# Rotary_Switches.net
KiCad netlist of a schematic drawn in Altium Designer
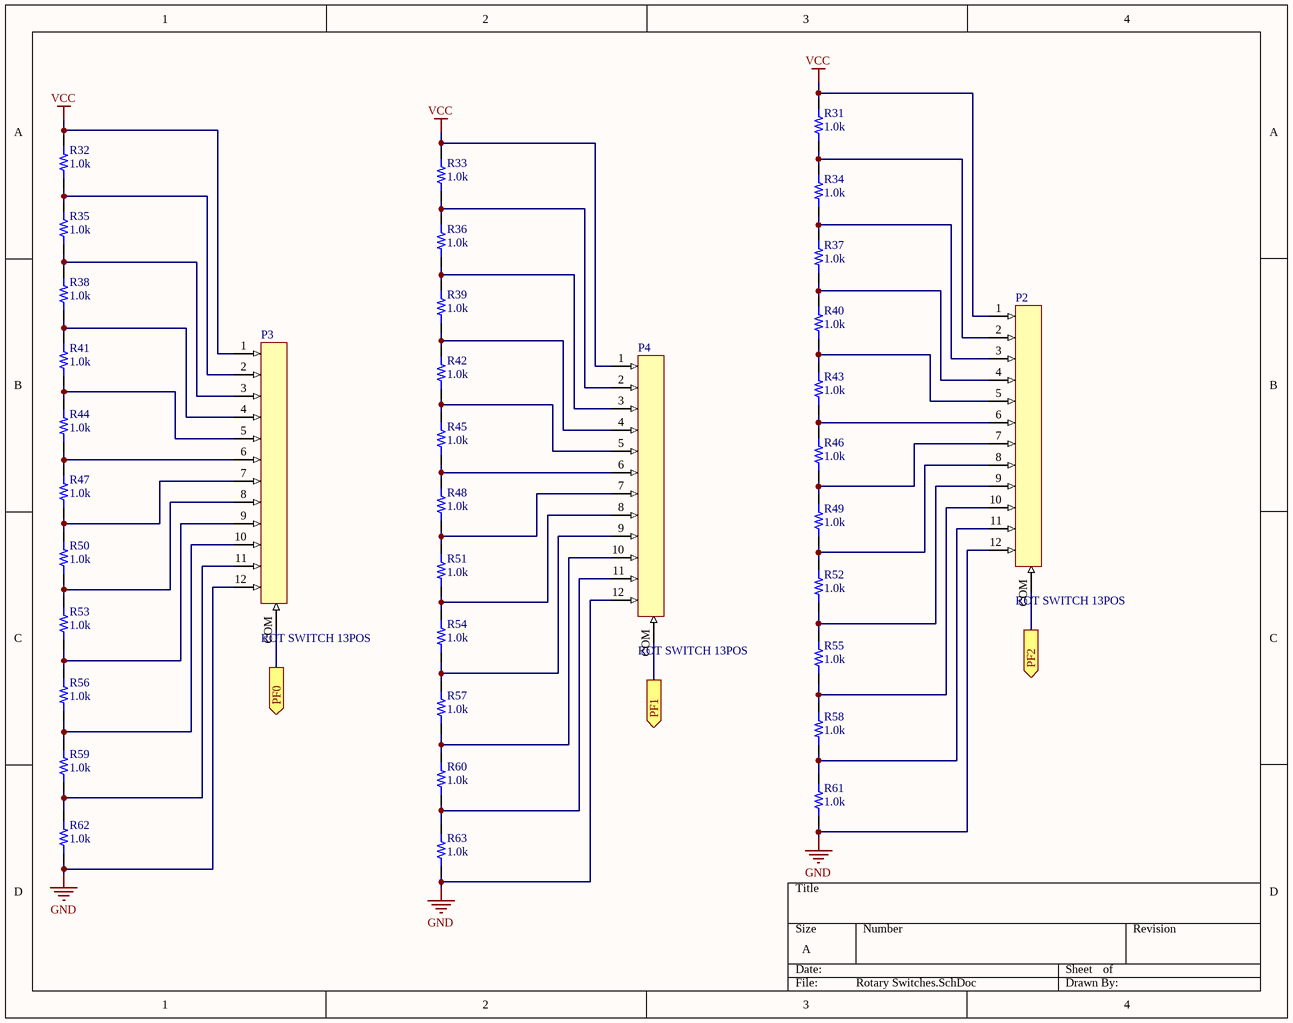
[diagram p0: Rotary Switches.SchDoc]

(export (version "E")
  (design (tool "Eeschema 10.0.6"))
  (components
    (comp (ref "P2")
      (value "ROT SWITCH 13POS")
      (footprint "ROT SWITCH 13POS")
      (fields (field (name "MFRPARTNO") "56DP30-01-1-AJN") (field (name "CREATED_BY") "Angel"))
      (libsource (lib "Altium-Lib") (part "ROT SWITCH 13POS"))
    )
    (comp (ref "P3")
      (value "ROT SWITCH 13POS")
      (footprint "ROT SWITCH 13POS")
      (fields (field (name "MFRPARTNO") "56DP30-01-1-AJN") (field (name "CREATED_BY") "Angel"))
      (libsource (lib "Altium-Lib") (part "ROT SWITCH 13POS"))
    )
    (comp (ref "P4")
      (value "ROT SWITCH 13POS")
      (footprint "ROT SWITCH 13POS")
      (fields (field (name "MFRPARTNO") "56DP30-01-1-AJN") (field (name "CREATED_BY") "Angel"))
      (libsource (lib "Altium-Lib") (part "ROT SWITCH 13POS"))
    )
    (comp (ref "R31")
      (value "1.0k")
      (footprint "RES 0603/1608")
      (fields
        (field (name "TOLERANCE") "1%")
        (field (name "POWER") "1/10W")
        (field (name "Comment") "Resistor 1.0k 0603 1/10W 1%")
        (field (name "CREATED_BY") "Nick Mah")
      )
      (libsource (lib "Altium-Lib") (part "Resistor"))
    )
    (comp (ref "R32")
      (value "1.0k")
      (footprint "RES 0603/1608")
      (fields
        (field (name "TOLERANCE") "1%")
        (field (name "POWER") "1/10W")
        (field (name "Comment") "Resistor 1.0k 0603 1/10W 1%")
        (field (name "CREATED_BY") "Nick Mah")
      )
      (libsource (lib "Altium-Lib") (part "Resistor"))
    )
    (comp (ref "R33")
      (value "1.0k")
      (footprint "RES 0603/1608")
      (fields
        (field (name "TOLERANCE") "1%")
        (field (name "POWER") "1/10W")
        (field (name "Comment") "Resistor 1.0k 0603 1/10W 1%")
        (field (name "CREATED_BY") "Nick Mah")
      )
      (libsource (lib "Altium-Lib") (part "Resistor"))
    )
    (comp (ref "R34")
      (value "1.0k")
      (footprint "RES 0603/1608")
      (fields
        (field (name "TOLERANCE") "1%")
        (field (name "POWER") "1/10W")
        (field (name "Comment") "Resistor 1.0k 0603 1/10W 1%")
        (field (name "CREATED_BY") "Nick Mah")
      )
      (libsource (lib "Altium-Lib") (part "Resistor"))
    )
    (comp (ref "R35")
      (value "1.0k")
      (footprint "RES 0603/1608")
      (fields
        (field (name "TOLERANCE") "1%")
        (field (name "POWER") "1/10W")
        (field (name "Comment") "Resistor 1.0k 0603 1/10W 1%")
        (field (name "CREATED_BY") "Nick Mah")
      )
      (libsource (lib "Altium-Lib") (part "Resistor"))
    )
    (comp (ref "R36")
      (value "1.0k")
      (footprint "RES 0603/1608")
      (fields
        (field (name "TOLERANCE") "1%")
        (field (name "POWER") "1/10W")
        (field (name "Comment") "Resistor 1.0k 0603 1/10W 1%")
        (field (name "CREATED_BY") "Nick Mah")
      )
      (libsource (lib "Altium-Lib") (part "Resistor"))
    )
    (comp (ref "R37")
      (value "1.0k")
      (footprint "RES 0603/1608")
      (fields
        (field (name "TOLERANCE") "1%")
        (field (name "POWER") "1/10W")
        (field (name "Comment") "Resistor 1.0k 0603 1/10W 1%")
        (field (name "CREATED_BY") "Nick Mah")
      )
      (libsource (lib "Altium-Lib") (part "Resistor"))
    )
    (comp (ref "R38")
      (value "1.0k")
      (footprint "RES 0603/1608")
      (fields
        (field (name "TOLERANCE") "1%")
        (field (name "POWER") "1/10W")
        (field (name "Comment") "Resistor 1.0k 0603 1/10W 1%")
        (field (name "CREATED_BY") "Nick Mah")
      )
      (libsource (lib "Altium-Lib") (part "Resistor"))
    )
    (comp (ref "R39")
      (value "1.0k")
      (footprint "RES 0603/1608")
      (fields
        (field (name "TOLERANCE") "1%")
        (field (name "POWER") "1/10W")
        (field (name "Comment") "Resistor 1.0k 0603 1/10W 1%")
        (field (name "CREATED_BY") "Nick Mah")
      )
      (libsource (lib "Altium-Lib") (part "Resistor"))
    )
    (comp (ref "R40")
      (value "1.0k")
      (footprint "RES 0603/1608")
      (fields
        (field (name "TOLERANCE") "1%")
        (field (name "POWER") "1/10W")
        (field (name "Comment") "Resistor 1.0k 0603 1/10W 1%")
        (field (name "CREATED_BY") "Nick Mah")
      )
      (libsource (lib "Altium-Lib") (part "Resistor"))
    )
    (comp (ref "R41")
      (value "1.0k")
      (footprint "RES 0603/1608")
      (fields
        (field (name "TOLERANCE") "1%")
        (field (name "POWER") "1/10W")
        (field (name "Comment") "Resistor 1.0k 0603 1/10W 1%")
        (field (name "CREATED_BY") "Nick Mah")
      )
      (libsource (lib "Altium-Lib") (part "Resistor"))
    )
    (comp (ref "R42")
      (value "1.0k")
      (footprint "RES 0603/1608")
      (fields
        (field (name "TOLERANCE") "1%")
        (field (name "POWER") "1/10W")
        (field (name "Comment") "Resistor 1.0k 0603 1/10W 1%")
        (field (name "CREATED_BY") "Nick Mah")
      )
      (libsource (lib "Altium-Lib") (part "Resistor"))
    )
    (comp (ref "R43")
      (value "1.0k")
      (footprint "RES 0603/1608")
      (fields
        (field (name "TOLERANCE") "1%")
        (field (name "POWER") "1/10W")
        (field (name "Comment") "Resistor 1.0k 0603 1/10W 1%")
        (field (name "CREATED_BY") "Nick Mah")
      )
      (libsource (lib "Altium-Lib") (part "Resistor"))
    )
    (comp (ref "R44")
      (value "1.0k")
      (footprint "RES 0603/1608")
      (fields
        (field (name "TOLERANCE") "1%")
        (field (name "POWER") "1/10W")
        (field (name "Comment") "Resistor 1.0k 0603 1/10W 1%")
        (field (name "CREATED_BY") "Nick Mah")
      )
      (libsource (lib "Altium-Lib") (part "Resistor"))
    )
    (comp (ref "R45")
      (value "1.0k")
      (footprint "RES 0603/1608")
      (fields
        (field (name "TOLERANCE") "1%")
        (field (name "POWER") "1/10W")
        (field (name "Comment") "Resistor 1.0k 0603 1/10W 1%")
        (field (name "CREATED_BY") "Nick Mah")
      )
      (libsource (lib "Altium-Lib") (part "Resistor"))
    )
    (comp (ref "R46")
      (value "1.0k")
      (footprint "RES 0603/1608")
      (fields
        (field (name "TOLERANCE") "1%")
        (field (name "POWER") "1/10W")
        (field (name "Comment") "Resistor 1.0k 0603 1/10W 1%")
        (field (name "CREATED_BY") "Nick Mah")
      )
      (libsource (lib "Altium-Lib") (part "Resistor"))
    )
    (comp (ref "R47")
      (value "1.0k")
      (footprint "RES 0603/1608")
      (fields
        (field (name "TOLERANCE") "1%")
        (field (name "POWER") "1/10W")
        (field (name "Comment") "Resistor 1.0k 0603 1/10W 1%")
        (field (name "CREATED_BY") "Nick Mah")
      )
      (libsource (lib "Altium-Lib") (part "Resistor"))
    )
    (comp (ref "R48")
      (value "1.0k")
      (footprint "RES 0603/1608")
      (fields
        (field (name "TOLERANCE") "1%")
        (field (name "POWER") "1/10W")
        (field (name "Comment") "Resistor 1.0k 0603 1/10W 1%")
        (field (name "CREATED_BY") "Nick Mah")
      )
      (libsource (lib "Altium-Lib") (part "Resistor"))
    )
    (comp (ref "R49")
      (value "1.0k")
      (footprint "RES 0603/1608")
      (fields
        (field (name "TOLERANCE") "1%")
        (field (name "POWER") "1/10W")
        (field (name "Comment") "Resistor 1.0k 0603 1/10W 1%")
        (field (name "CREATED_BY") "Nick Mah")
      )
      (libsource (lib "Altium-Lib") (part "Resistor"))
    )
    (comp (ref "R50")
      (value "1.0k")
      (footprint "RES 0603/1608")
      (fields
        (field (name "TOLERANCE") "1%")
        (field (name "POWER") "1/10W")
        (field (name "Comment") "Resistor 1.0k 0603 1/10W 1%")
        (field (name "CREATED_BY") "Nick Mah")
      )
      (libsource (lib "Altium-Lib") (part "Resistor"))
    )
    (comp (ref "R51")
      (value "1.0k")
      (footprint "RES 0603/1608")
      (fields
        (field (name "TOLERANCE") "1%")
        (field (name "POWER") "1/10W")
        (field (name "Comment") "Resistor 1.0k 0603 1/10W 1%")
        (field (name "CREATED_BY") "Nick Mah")
      )
      (libsource (lib "Altium-Lib") (part "Resistor"))
    )
    (comp (ref "R52")
      (value "1.0k")
      (footprint "RES 0603/1608")
      (fields
        (field (name "TOLERANCE") "1%")
        (field (name "POWER") "1/10W")
        (field (name "Comment") "Resistor 1.0k 0603 1/10W 1%")
        (field (name "CREATED_BY") "Nick Mah")
      )
      (libsource (lib "Altium-Lib") (part "Resistor"))
    )
    (comp (ref "R53")
      (value "1.0k")
      (footprint "RES 0603/1608")
      (fields
        (field (name "TOLERANCE") "1%")
        (field (name "POWER") "1/10W")
        (field (name "Comment") "Resistor 1.0k 0603 1/10W 1%")
        (field (name "CREATED_BY") "Nick Mah")
      )
      (libsource (lib "Altium-Lib") (part "Resistor"))
    )
    (comp (ref "R54")
      (value "1.0k")
      (footprint "RES 0603/1608")
      (fields
        (field (name "TOLERANCE") "1%")
        (field (name "POWER") "1/10W")
        (field (name "Comment") "Resistor 1.0k 0603 1/10W 1%")
        (field (name "CREATED_BY") "Nick Mah")
      )
      (libsource (lib "Altium-Lib") (part "Resistor"))
    )
    (comp (ref "R55")
      (value "1.0k")
      (footprint "RES 0603/1608")
      (fields
        (field (name "TOLERANCE") "1%")
        (field (name "POWER") "1/10W")
        (field (name "Comment") "Resistor 1.0k 0603 1/10W 1%")
        (field (name "CREATED_BY") "Nick Mah")
      )
      (libsource (lib "Altium-Lib") (part "Resistor"))
    )
    (comp (ref "R56")
      (value "1.0k")
      (footprint "RES 0603/1608")
      (fields
        (field (name "TOLERANCE") "1%")
        (field (name "POWER") "1/10W")
        (field (name "Comment") "Resistor 1.0k 0603 1/10W 1%")
        (field (name "CREATED_BY") "Nick Mah")
      )
      (libsource (lib "Altium-Lib") (part "Resistor"))
    )
    (comp (ref "R57")
      (value "1.0k")
      (footprint "RES 0603/1608")
      (fields
        (field (name "TOLERANCE") "1%")
        (field (name "POWER") "1/10W")
        (field (name "Comment") "Resistor 1.0k 0603 1/10W 1%")
        (field (name "CREATED_BY") "Nick Mah")
      )
      (libsource (lib "Altium-Lib") (part "Resistor"))
    )
    (comp (ref "R58")
      (value "1.0k")
      (footprint "RES 0603/1608")
      (fields
        (field (name "TOLERANCE") "1%")
        (field (name "POWER") "1/10W")
        (field (name "Comment") "Resistor 1.0k 0603 1/10W 1%")
        (field (name "CREATED_BY") "Nick Mah")
      )
      (libsource (lib "Altium-Lib") (part "Resistor"))
    )
    (comp (ref "R59")
      (value "1.0k")
      (footprint "RES 0603/1608")
      (fields
        (field (name "TOLERANCE") "1%")
        (field (name "POWER") "1/10W")
        (field (name "Comment") "Resistor 1.0k 0603 1/10W 1%")
        (field (name "CREATED_BY") "Nick Mah")
      )
      (libsource (lib "Altium-Lib") (part "Resistor"))
    )
    (comp (ref "R60")
      (value "1.0k")
      (footprint "RES 0603/1608")
      (fields
        (field (name "TOLERANCE") "1%")
        (field (name "POWER") "1/10W")
        (field (name "Comment") "Resistor 1.0k 0603 1/10W 1%")
        (field (name "CREATED_BY") "Nick Mah")
      )
      (libsource (lib "Altium-Lib") (part "Resistor"))
    )
    (comp (ref "R61")
      (value "1.0k")
      (footprint "RES 0603/1608")
      (fields
        (field (name "TOLERANCE") "1%")
        (field (name "POWER") "1/10W")
        (field (name "Comment") "Resistor 1.0k 0603 1/10W 1%")
        (field (name "CREATED_BY") "Nick Mah")
      )
      (libsource (lib "Altium-Lib") (part "Resistor"))
    )
    (comp (ref "R62")
      (value "1.0k")
      (footprint "RES 0603/1608")
      (fields
        (field (name "TOLERANCE") "1%")
        (field (name "POWER") "1/10W")
        (field (name "Comment") "Resistor 1.0k 0603 1/10W 1%")
        (field (name "CREATED_BY") "Nick Mah")
      )
      (libsource (lib "Altium-Lib") (part "Resistor"))
    )
    (comp (ref "R63")
      (value "1.0k")
      (footprint "RES 0603/1608")
      (fields
        (field (name "TOLERANCE") "1%")
        (field (name "POWER") "1/10W")
        (field (name "Comment") "Resistor 1.0k 0603 1/10W 1%")
        (field (name "CREATED_BY") "Nick Mah")
      )
      (libsource (lib "Altium-Lib") (part "Resistor"))
    )
  )
  (nets
    (net (code "1") (name "/PF0") (class "Default") (node (ref "P3") (pin "COM") (pintype "input")))
    (net (code "2") (name "/PF1") (class "Default") (node (ref "P4") (pin "COM") (pintype "input")))
    (net (code "3") (name "/PF2") (class "Default") (node (ref "P2") (pin "COM") (pintype "input")))
    (net (code "4") (name "GND") (class "Default")
      (node (ref "P2") (pin "12") (pintype "input"))
      (node (ref "P3") (pin "12") (pintype "input"))
      (node (ref "P4") (pin "12") (pintype "input"))
      (node (ref "R61") (pin "2") (pinfunction "2_2") (pintype "passive"))
      (node (ref "R62") (pin "2") (pinfunction "2_2") (pintype "passive"))
      (node (ref "R63") (pin "2") (pinfunction "2_2") (pintype "passive"))
    )
    (net (code "5") (name "Net-(P2-Pad2)") (class "Default")
      (node (ref "P2") (pin "2") (pintype "input"))
      (node (ref "R31") (pin "2") (pinfunction "2_2") (pintype "passive"))
      (node (ref "R34") (pin "1") (pinfunction "1_1") (pintype "passive"))
    )
    (net (code "6") (name "Net-(P2-Pad3)") (class "Default")
      (node (ref "P2") (pin "3") (pintype "input"))
      (node (ref "R34") (pin "2") (pinfunction "2_2") (pintype "passive"))
      (node (ref "R37") (pin "1") (pinfunction "1_1") (pintype "passive"))
    )
    (net (code "7") (name "Net-(P2-Pad4)") (class "Default")
      (node (ref "P2") (pin "4") (pintype "input"))
      (node (ref "R37") (pin "2") (pinfunction "2_2") (pintype "passive"))
      (node (ref "R40") (pin "1") (pinfunction "1_1") (pintype "passive"))
    )
    (net (code "8") (name "Net-(P2-Pad5)") (class "Default")
      (node (ref "P2") (pin "5") (pintype "input"))
      (node (ref "R40") (pin "2") (pinfunction "2_2") (pintype "passive"))
      (node (ref "R43") (pin "1") (pinfunction "1_1") (pintype "passive"))
    )
    (net (code "9") (name "Net-(P2-Pad6)") (class "Default")
      (node (ref "P2") (pin "6") (pintype "input"))
      (node (ref "R43") (pin "2") (pinfunction "2_2") (pintype "passive"))
      (node (ref "R46") (pin "1") (pinfunction "1_1") (pintype "passive"))
    )
    (net (code "10") (name "Net-(P2-Pad7)") (class "Default")
      (node (ref "P2") (pin "7") (pintype "input"))
      (node (ref "R46") (pin "2") (pinfunction "2_2") (pintype "passive"))
      (node (ref "R49") (pin "1") (pinfunction "1_1") (pintype "passive"))
    )
    (net (code "11") (name "Net-(P2-Pad8)") (class "Default")
      (node (ref "P2") (pin "8") (pintype "input"))
      (node (ref "R49") (pin "2") (pinfunction "2_2") (pintype "passive"))
      (node (ref "R52") (pin "1") (pinfunction "1_1") (pintype "passive"))
    )
    (net (code "12") (name "Net-(P2-Pad9)") (class "Default")
      (node (ref "P2") (pin "9") (pintype "input"))
      (node (ref "R52") (pin "2") (pinfunction "2_2") (pintype "passive"))
      (node (ref "R55") (pin "1") (pinfunction "1_1") (pintype "passive"))
    )
    (net (code "13") (name "Net-(P2-Pad10)") (class "Default")
      (node (ref "P2") (pin "10") (pintype "input"))
      (node (ref "R55") (pin "2") (pinfunction "2_2") (pintype "passive"))
      (node (ref "R58") (pin "1") (pinfunction "1_1") (pintype "passive"))
    )
    (net (code "14") (name "Net-(P2-Pad11)") (class "Default")
      (node (ref "P2") (pin "11") (pintype "input"))
      (node (ref "R58") (pin "2") (pinfunction "2_2") (pintype "passive"))
      (node (ref "R61") (pin "1") (pinfunction "1_1") (pintype "passive"))
    )
    (net (code "15") (name "Net-(P3-Pad2)") (class "Default")
      (node (ref "P3") (pin "2") (pintype "input"))
      (node (ref "R32") (pin "2") (pinfunction "2_2") (pintype "passive"))
      (node (ref "R35") (pin "1") (pinfunction "1_1") (pintype "passive"))
    )
    (net (code "16") (name "Net-(P3-Pad3)") (class "Default")
      (node (ref "P3") (pin "3") (pintype "input"))
      (node (ref "R35") (pin "2") (pinfunction "2_2") (pintype "passive"))
      (node (ref "R38") (pin "1") (pinfunction "1_1") (pintype "passive"))
    )
    (net (code "17") (name "Net-(P3-Pad4)") (class "Default")
      (node (ref "P3") (pin "4") (pintype "input"))
      (node (ref "R38") (pin "2") (pinfunction "2_2") (pintype "passive"))
      (node (ref "R41") (pin "1") (pinfunction "1_1") (pintype "passive"))
    )
    (net (code "18") (name "Net-(P3-Pad5)") (class "Default")
      (node (ref "P3") (pin "5") (pintype "input"))
      (node (ref "R41") (pin "2") (pinfunction "2_2") (pintype "passive"))
      (node (ref "R44") (pin "1") (pinfunction "1_1") (pintype "passive"))
    )
    (net (code "19") (name "Net-(P3-Pad6)") (class "Default")
      (node (ref "P3") (pin "6") (pintype "input"))
      (node (ref "R44") (pin "2") (pinfunction "2_2") (pintype "passive"))
      (node (ref "R47") (pin "1") (pinfunction "1_1") (pintype "passive"))
    )
    (net (code "20") (name "Net-(P3-Pad7)") (class "Default")
      (node (ref "P3") (pin "7") (pintype "input"))
      (node (ref "R47") (pin "2") (pinfunction "2_2") (pintype "passive"))
      (node (ref "R50") (pin "1") (pinfunction "1_1") (pintype "passive"))
    )
    (net (code "21") (name "Net-(P3-Pad8)") (class "Default")
      (node (ref "P3") (pin "8") (pintype "input"))
      (node (ref "R50") (pin "2") (pinfunction "2_2") (pintype "passive"))
      (node (ref "R53") (pin "1") (pinfunction "1_1") (pintype "passive"))
    )
    (net (code "22") (name "Net-(P3-Pad9)") (class "Default")
      (node (ref "P3") (pin "9") (pintype "input"))
      (node (ref "R53") (pin "2") (pinfunction "2_2") (pintype "passive"))
      (node (ref "R56") (pin "1") (pinfunction "1_1") (pintype "passive"))
    )
    (net (code "23") (name "Net-(P3-Pad10)") (class "Default")
      (node (ref "P3") (pin "10") (pintype "input"))
      (node (ref "R56") (pin "2") (pinfunction "2_2") (pintype "passive"))
      (node (ref "R59") (pin "1") (pinfunction "1_1") (pintype "passive"))
    )
    (net (code "24") (name "Net-(P3-Pad11)") (class "Default")
      (node (ref "P3") (pin "11") (pintype "input"))
      (node (ref "R59") (pin "2") (pinfunction "2_2") (pintype "passive"))
      (node (ref "R62") (pin "1") (pinfunction "1_1") (pintype "passive"))
    )
    (net (code "25") (name "Net-(P4-Pad2)") (class "Default")
      (node (ref "P4") (pin "2") (pintype "input"))
      (node (ref "R33") (pin "2") (pinfunction "2_2") (pintype "passive"))
      (node (ref "R36") (pin "1") (pinfunction "1_1") (pintype "passive"))
    )
    (net (code "26") (name "Net-(P4-Pad3)") (class "Default")
      (node (ref "P4") (pin "3") (pintype "input"))
      (node (ref "R36") (pin "2") (pinfunction "2_2") (pintype "passive"))
      (node (ref "R39") (pin "1") (pinfunction "1_1") (pintype "passive"))
    )
    (net (code "27") (name "Net-(P4-Pad4)") (class "Default")
      (node (ref "P4") (pin "4") (pintype "input"))
      (node (ref "R39") (pin "2") (pinfunction "2_2") (pintype "passive"))
      (node (ref "R42") (pin "1") (pinfunction "1_1") (pintype "passive"))
    )
    (net (code "28") (name "Net-(P4-Pad5)") (class "Default")
      (node (ref "P4") (pin "5") (pintype "input"))
      (node (ref "R42") (pin "2") (pinfunction "2_2") (pintype "passive"))
      (node (ref "R45") (pin "1") (pinfunction "1_1") (pintype "passive"))
    )
    (net (code "29") (name "Net-(P4-Pad6)") (class "Default")
      (node (ref "P4") (pin "6") (pintype "input"))
      (node (ref "R45") (pin "2") (pinfunction "2_2") (pintype "passive"))
      (node (ref "R48") (pin "1") (pinfunction "1_1") (pintype "passive"))
    )
    (net (code "30") (name "Net-(P4-Pad7)") (class "Default")
      (node (ref "P4") (pin "7") (pintype "input"))
      (node (ref "R48") (pin "2") (pinfunction "2_2") (pintype "passive"))
      (node (ref "R51") (pin "1") (pinfunction "1_1") (pintype "passive"))
    )
    (net (code "31") (name "Net-(P4-Pad8)") (class "Default")
      (node (ref "P4") (pin "8") (pintype "input"))
      (node (ref "R51") (pin "2") (pinfunction "2_2") (pintype "passive"))
      (node (ref "R54") (pin "1") (pinfunction "1_1") (pintype "passive"))
    )
    (net (code "32") (name "Net-(P4-Pad9)") (class "Default")
      (node (ref "P4") (pin "9") (pintype "input"))
      (node (ref "R54") (pin "2") (pinfunction "2_2") (pintype "passive"))
      (node (ref "R57") (pin "1") (pinfunction "1_1") (pintype "passive"))
    )
    (net (code "33") (name "Net-(P4-Pad10)") (class "Default")
      (node (ref "P4") (pin "10") (pintype "input"))
      (node (ref "R57") (pin "2") (pinfunction "2_2") (pintype "passive"))
      (node (ref "R60") (pin "1") (pinfunction "1_1") (pintype "passive"))
    )
    (net (code "34") (name "Net-(P4-Pad11)") (class "Default")
      (node (ref "P4") (pin "11") (pintype "input"))
      (node (ref "R60") (pin "2") (pinfunction "2_2") (pintype "passive"))
      (node (ref "R63") (pin "1") (pinfunction "1_1") (pintype "passive"))
    )
    (net (code "35") (name "VCC") (class "Default")
      (node (ref "P2") (pin "1") (pintype "input"))
      (node (ref "P3") (pin "1") (pintype "input"))
      (node (ref "P4") (pin "1") (pintype "input"))
      (node (ref "R31") (pin "1") (pinfunction "1_1") (pintype "passive"))
      (node (ref "R32") (pin "1") (pinfunction "1_1") (pintype "passive"))
      (node (ref "R33") (pin "1") (pinfunction "1_1") (pintype "passive"))
    )
  )
)
